# BeaconKeyer_RevB.net
KiCad netlist of a schematic drawn in EAGLE
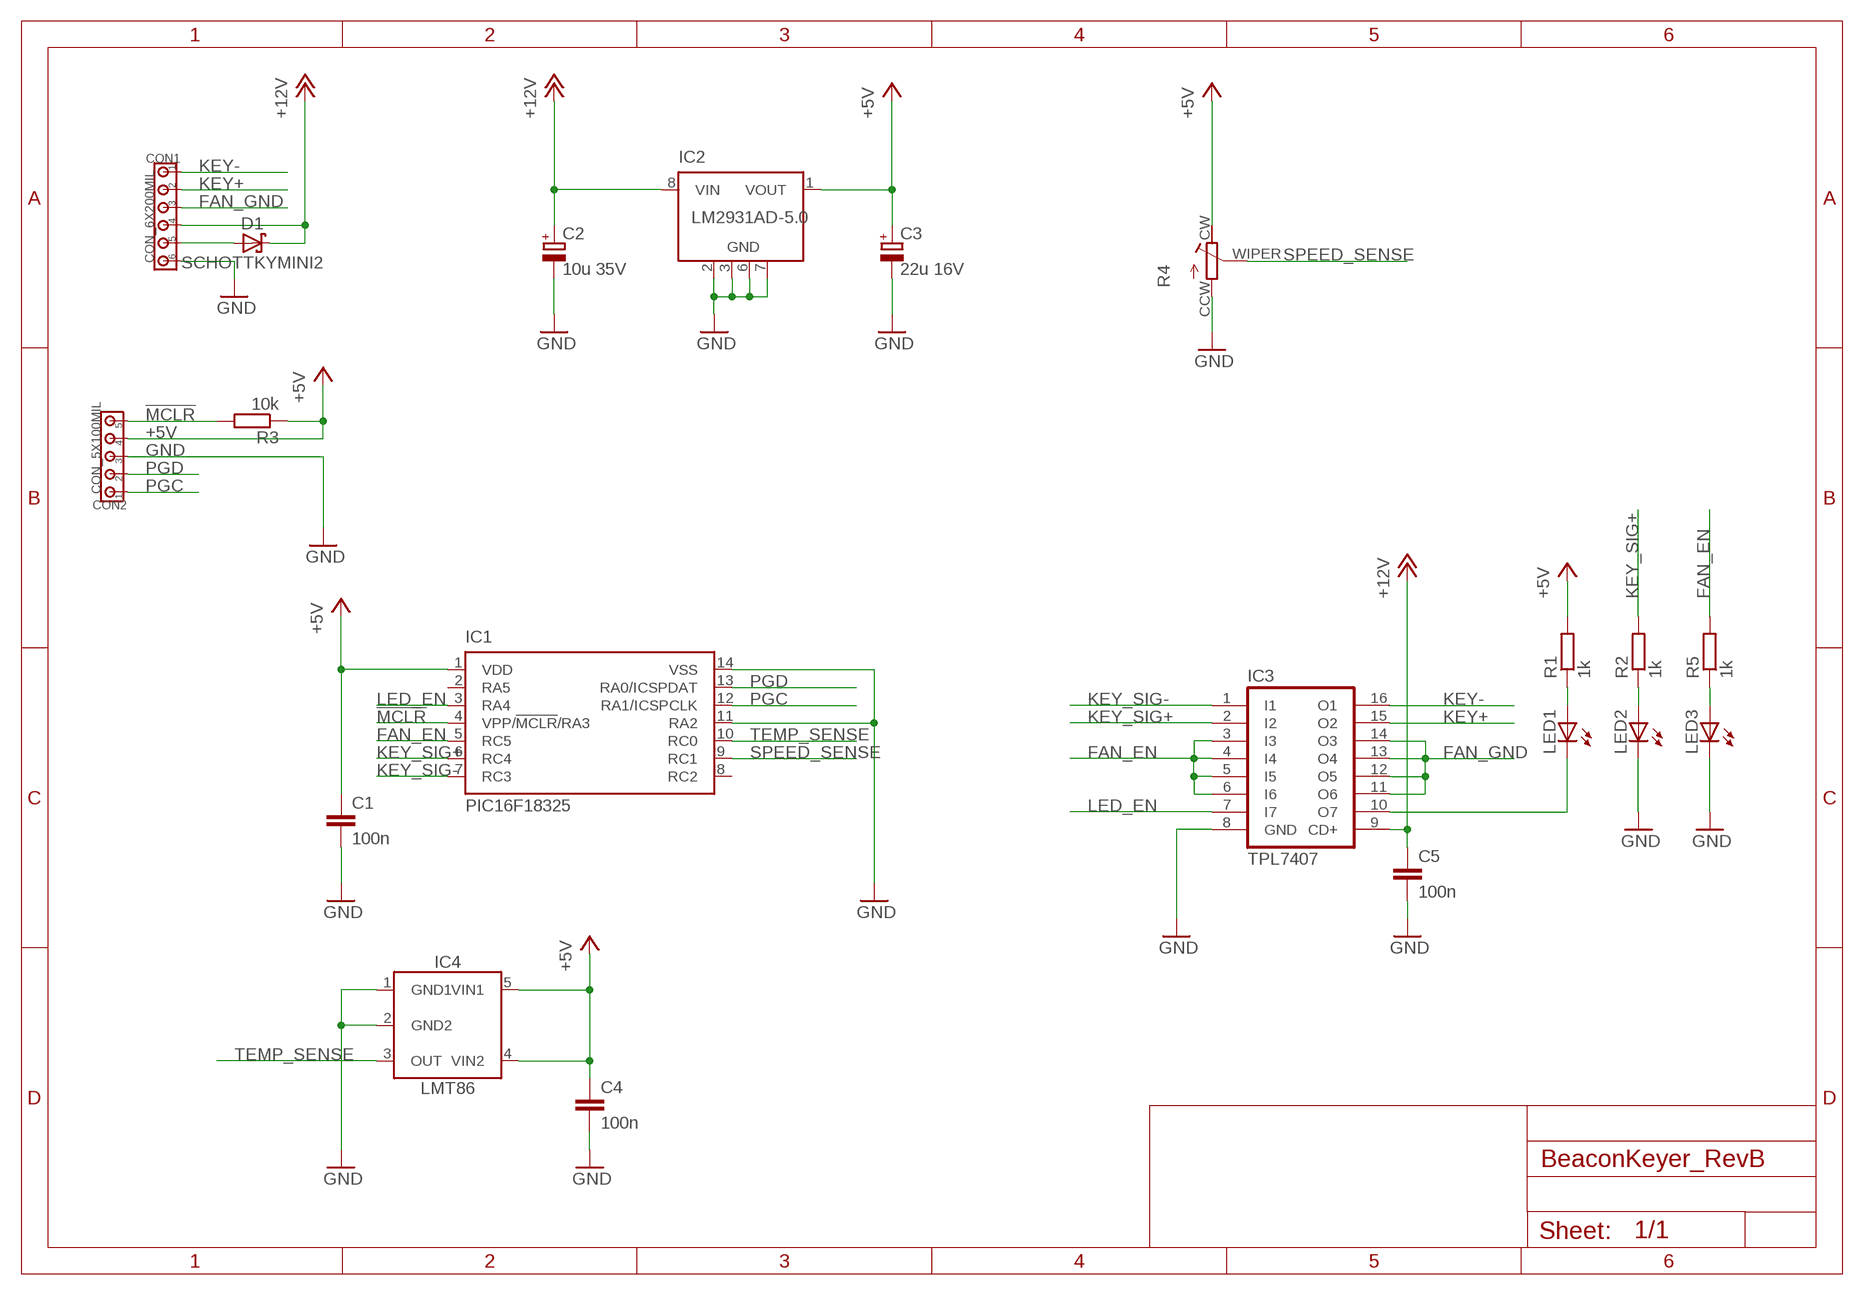
[diagram p0: schematic, sheet 1]

(export (version "E")
  (design (tool "Eeschema 10.0.6"))
  (components
    (comp (ref "C1")
      (value "100n")
      (footprint "eagle-import:C0805")
      (libsource (lib "eagle-import") (part "CC0805"))
    )
    (comp (ref "C2")
      (value "10u 35V")
      (footprint "eagle-import:SMC_C")
      (libsource (lib "eagle-import") (part "C_POLARIZEDSMC_C"))
    )
    (comp (ref "C3")
      (value "22u 16V")
      (footprint "eagle-import:SMC_C")
      (libsource (lib "eagle-import") (part "C_POLARIZEDSMC_C"))
    )
    (comp (ref "C4")
      (value "100n")
      (footprint "eagle-import:C0805")
      (libsource (lib "eagle-import") (part "CC0805"))
    )
    (comp (ref "C5")
      (value "100n")
      (footprint "eagle-import:C0805")
      (libsource (lib "eagle-import") (part "CC0805"))
    )
    (comp (ref "CON1")
      (value "CON_6X200MIL")
      (footprint "eagle-import:200MIL_6X")
      (libsource (lib "eagle-import") (part "CON_6X200MIL"))
    )
    (comp (ref "CON2")
      (value "CON_5X100MIL")
      (footprint "eagle-import:100MIL_5X")
      (libsource (lib "eagle-import") (part "CON_5X100MIL"))
    )
    (comp (ref "D1")
      (value "SCHOTTKYMINI2")
      (footprint "eagle-import:MINI2-F3-B")
      (libsource (lib "eagle-import") (part "SCHOTTKYMINI2"))
    )
    (comp (ref "IC1")
      (value "PIC16F18325")
      (footprint "eagle-import:SO14")
      (libsource (lib "eagle-import") (part "PIC16F18325"))
    )
    (comp (ref "IC2")
      (value "LM2931AD-5.0")
      (footprint "eagle-import:SOIC8")
      (libsource (lib "eagle-import") (part "LM2931AD-5.0"))
    )
    (comp (ref "IC3")
      (value "TPL7407")
      (footprint "eagle-import:SO16")
      (libsource (lib "eagle-import") (part "ULN2003"))
    )
    (comp (ref "IC4")
      (value "LMT86")
      (footprint "eagle-import:SC70-5")
      (libsource (lib "eagle-import") (part "LMT86"))
    )
    (comp (ref "LED1")
      (value "LED0805")
      (footprint "eagle-import:LED0805")
      (libsource (lib "eagle-import") (part "LED0805"))
    )
    (comp (ref "LED2")
      (value "LED0805")
      (footprint "eagle-import:LED0805")
      (libsource (lib "eagle-import") (part "LED0805"))
    )
    (comp (ref "LED3")
      (value "LED0805")
      (footprint "eagle-import:LED0805")
      (libsource (lib "eagle-import") (part "LED0805"))
    )
    (comp (ref "R1")
      (value "1k")
      (footprint "eagle-import:R0805")
      (libsource (lib "eagle-import") (part "RESISTORR0805"))
    )
    (comp (ref "R2")
      (value "1k")
      (footprint "eagle-import:R0805")
      (libsource (lib "eagle-import") (part "RESISTORR0805"))
    )
    (comp (ref "R3")
      (value "10k")
      (footprint "eagle-import:R0805")
      (libsource (lib "eagle-import") (part "RESISTORR0805"))
    )
    (comp (ref "R4")
      (value "TRIMMER3314G")
      (footprint "eagle-import:RTRIM3314G")
      (libsource (lib "eagle-import") (part "TRIMMER3314G"))
    )
    (comp (ref "R5")
      (value "1k")
      (footprint "eagle-import:R0805")
      (libsource (lib "eagle-import") (part "RESISTORR0805"))
    )
  )
  (nets
    (net (code "1") (name "+5V") (class "Default")
      (node (ref "C1") (pin "1") (pinfunction "1_1") (pintype "passive"))
      (node (ref "C3") (pin "+") (pinfunction "+_+") (pintype "passive"))
      (node (ref "C4") (pin "1") (pinfunction "1_1") (pintype "passive"))
      (node (ref "CON2") (pin "4") (pinfunction "4_4") (pintype "passive"))
      (node (ref "IC1") (pin "1") (pinfunction "VDD_1") (pintype "power_in"))
      (node (ref "IC2") (pin "1") (pinfunction "VOUT_1") (pintype "output"))
      (node (ref "IC4") (pin "4") (pinfunction "VIN2_4") (pintype "passive"))
      (node (ref "IC4") (pin "5") (pinfunction "VIN1_5") (pintype "input"))
      (node (ref "R1") (pin "2") (pinfunction "2_2") (pintype "passive"))
      (node (ref "R3") (pin "1") (pinfunction "1_1") (pintype "passive"))
      (node (ref "R4") (pin "CW") (pinfunction "CW_CW") (pintype "passive"))
    )
    (net (code "2") (name "+12V") (class "Default")
      (node (ref "C2") (pin "+") (pinfunction "+_+") (pintype "passive"))
      (node (ref "C5") (pin "1") (pinfunction "1_1") (pintype "passive"))
      (node (ref "CON1") (pin "4") (pinfunction "4_4") (pintype "passive"))
      (node (ref "D1") (pin "C") (pinfunction "C_C") (pintype "passive"))
      (node (ref "IC2") (pin "8") (pinfunction "VIN_8") (pintype "passive"))
      (node (ref "IC3") (pin "9") (pinfunction "CD+_9") (pintype "passive"))
    )
    (net (code "3") (name "/FAN_EN") (class "Default")
      (node (ref "IC1") (pin "5") (pinfunction "RC5_5") (pintype "bidirectional"))
      (node (ref "IC3") (pin "3") (pinfunction "I3_3") (pintype "input"))
      (node (ref "IC3") (pin "4") (pinfunction "I4_4") (pintype "input"))
      (node (ref "IC3") (pin "5") (pinfunction "I5_5") (pintype "input"))
      (node (ref "IC3") (pin "6") (pinfunction "I6_6") (pintype "input"))
      (node (ref "R5") (pin "2") (pinfunction "2_2") (pintype "passive"))
    )
    (net (code "4") (name "/FAN_GND") (class "Default")
      (node (ref "CON1") (pin "3") (pinfunction "3_3") (pintype "passive"))
      (node (ref "IC3") (pin "11") (pinfunction "O6_11") (pintype "open_collector"))
      (node (ref "IC3") (pin "12") (pinfunction "O5_12") (pintype "open_collector"))
      (node (ref "IC3") (pin "13") (pinfunction "O4_13") (pintype "open_collector"))
      (node (ref "IC3") (pin "14") (pinfunction "O3_14") (pintype "open_collector"))
    )
    (net (code "5") (name "/KEY+") (class "Default")
      (node (ref "CON1") (pin "2") (pinfunction "2_2") (pintype "passive"))
      (node (ref "IC3") (pin "15") (pinfunction "O2_15") (pintype "open_collector"))
    )
    (net (code "6") (name "/KEY-") (class "Default")
      (node (ref "CON1") (pin "1") (pinfunction "1_1") (pintype "passive"))
      (node (ref "IC3") (pin "16") (pinfunction "O1_16") (pintype "open_collector"))
    )
    (net (code "7") (name "/KEY_SIG+") (class "Default")
      (node (ref "IC1") (pin "6") (pinfunction "RC4_6") (pintype "bidirectional"))
      (node (ref "IC3") (pin "2") (pinfunction "I2_2") (pintype "input"))
      (node (ref "R2") (pin "2") (pinfunction "2_2") (pintype "passive"))
    )
    (net (code "8") (name "/KEY_SIG-") (class "Default")
      (node (ref "IC1") (pin "7") (pinfunction "RC3_7") (pintype "bidirectional"))
      (node (ref "IC3") (pin "1") (pinfunction "I1_1") (pintype "input"))
    )
    (net (code "9") (name "/LED_EN") (class "Default")
      (node (ref "IC1") (pin "3") (pinfunction "RA4_3") (pintype "bidirectional"))
      (node (ref "IC3") (pin "7") (pinfunction "I7_7") (pintype "input"))
    )
    (net (code "10") (name "/PGC") (class "Default")
      (node (ref "CON2") (pin "1") (pinfunction "1_1") (pintype "passive"))
      (node (ref "IC1") (pin "12") (pinfunction "RA1/ICSPCLK_12") (pintype "bidirectional"))
    )
    (net (code "11") (name "/PGD") (class "Default")
      (node (ref "CON2") (pin "2") (pinfunction "2_2") (pintype "passive"))
      (node (ref "IC1") (pin "13") (pinfunction "RA0/ICSPDAT_13") (pintype "bidirectional"))
    )
    (net (code "12") (name "/SPEED_SENSE") (class "Default")
      (node (ref "IC1") (pin "9") (pinfunction "RC1_9") (pintype "bidirectional"))
      (node (ref "R4") (pin "WIPER") (pinfunction "WIPER_WIPER") (pintype "passive"))
    )
    (net (code "13") (name "/TEMP_SENSE") (class "Default")
      (node (ref "IC1") (pin "10") (pinfunction "RC0_10") (pintype "bidirectional"))
      (node (ref "IC4") (pin "3") (pinfunction "OUT_3") (pintype "input"))
    )
    (net (code "14") (name "/~{MCLR}") (class "Default")
      (node (ref "CON2") (pin "5") (pinfunction "5_5") (pintype "passive"))
      (node (ref "IC1") (pin "4") (pinfunction "VPP/~{MCLR}/RA3_4") (pintype "bidirectional"))
      (node (ref "R3") (pin "2") (pinfunction "2_2") (pintype "passive"))
    )
    (net (code "15") (name "GND") (class "Default")
      (node (ref "C1") (pin "2") (pinfunction "2_2") (pintype "passive"))
      (node (ref "C2") (pin "-") (pinfunction "-_-") (pintype "passive"))
      (node (ref "C3") (pin "-") (pinfunction "-_-") (pintype "passive"))
      (node (ref "C4") (pin "2") (pinfunction "2_2") (pintype "passive"))
      (node (ref "C5") (pin "2") (pinfunction "2_2") (pintype "passive"))
      (node (ref "CON1") (pin "6") (pinfunction "6_6") (pintype "passive"))
      (node (ref "CON2") (pin "3") (pinfunction "3_3") (pintype "passive"))
      (node (ref "IC1") (pin "11") (pinfunction "RA2_11") (pintype "bidirectional"))
      (node (ref "IC1") (pin "14") (pinfunction "VSS_14") (pintype "power_in"))
      (node (ref "IC2") (pin "2") (pinfunction "GND_2") (pintype "power_in"))
      (node (ref "IC2") (pin "3") (pinfunction "GND_3") (pintype "power_in"))
      (node (ref "IC2") (pin "6") (pinfunction "GND_6") (pintype "power_in"))
      (node (ref "IC2") (pin "7") (pinfunction "GND_7") (pintype "power_in"))
      (node (ref "IC3") (pin "8") (pinfunction "GND_8") (pintype "power_in"))
      (node (ref "IC4") (pin "1") (pinfunction "GND1_1") (pintype "power_in"))
      (node (ref "IC4") (pin "2") (pinfunction "GND2_2") (pintype "power_in"))
      (node (ref "LED2") (pin "C") (pinfunction "C_C") (pintype "passive"))
      (node (ref "LED3") (pin "C") (pinfunction "C_C") (pintype "passive"))
      (node (ref "R4") (pin "CCW") (pinfunction "CCW_CCW") (pintype "passive"))
    )
    (net (code "16") (name "Net-(CON1-Pad5)") (class "Default")
      (node (ref "CON1") (pin "5") (pinfunction "5_5") (pintype "passive"))
      (node (ref "D1") (pin "A") (pinfunction "A_A") (pintype "passive"))
    )
    (net (code "17") (name "Net-(IC3-O7)") (class "Default")
      (node (ref "IC3") (pin "10") (pinfunction "O7_10") (pintype "open_collector"))
      (node (ref "LED1") (pin "C") (pinfunction "C_C") (pintype "passive"))
    )
    (net (code "18") (name "Net-(LED1-PadA)") (class "Default")
      (node (ref "LED1") (pin "A") (pinfunction "A_A") (pintype "passive"))
      (node (ref "R1") (pin "1") (pinfunction "1_1") (pintype "passive"))
    )
    (net (code "19") (name "Net-(LED2-PadA)") (class "Default")
      (node (ref "LED2") (pin "A") (pinfunction "A_A") (pintype "passive"))
      (node (ref "R2") (pin "1") (pinfunction "1_1") (pintype "passive"))
    )
    (net (code "20") (name "Net-(LED3-PadA)") (class "Default")
      (node (ref "LED3") (pin "A") (pinfunction "A_A") (pintype "passive"))
      (node (ref "R5") (pin "1") (pinfunction "1_1") (pintype "passive"))
    )
    (net (code "21") (name "unconnected-(IC1-RA5-Pad2)") (class "Default")
      (node (ref "IC1") (pin "2") (pinfunction "RA5_2") (pintype "input"))
    )
    (net (code "22") (name "unconnected-(IC1-RC2-Pad8)") (class "Default")
      (node (ref "IC1") (pin "8") (pinfunction "RC2_8") (pintype "bidirectional"))
    )
  )
)
